# Buck_Converter.net
KiCad netlist of a schematic drawn in Altium Designer
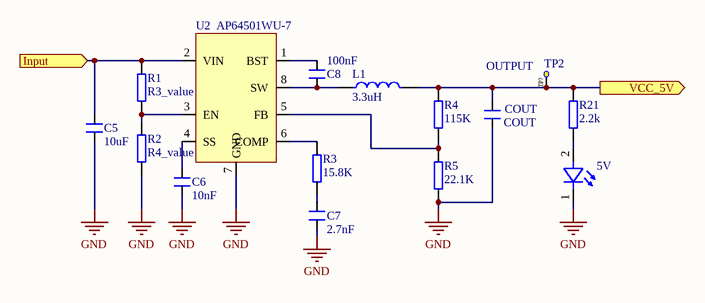
[diagram p0: Buck_Converter.SchDoc]

(export (version "E")
  (design (tool "Eeschema 10.0.6"))
  (components
    (comp (ref "5V") (value "led") (footprint "LED_fp") (libsource (lib "sch_comp") (part "led")))
    (comp (ref "C5") (value "10uF") (footprint "CAP_0805") (libsource (lib "sch_comp") (part "CAP_0805")))
    (comp (ref "C6") (value "10nF") (footprint "CAP_0805") (libsource (lib "sch_comp") (part "CAP_0805")))
    (comp (ref "C7") (value "2.7nF") (footprint "CAP_0805") (libsource (lib "sch_comp") (part "CAP_0805")))
    (comp (ref "C8") (value "100nF") (footprint "CAP_0805") (libsource (lib "sch_comp") (part "CAP_0805")))
    (comp (ref "COUT") (value "COUT") (footprint "CAP_0805") (libsource (lib "sch_comp") (part "CAP_0805")))
    (comp (ref "L1")
      (value "3.3uH")
      (footprint "SRN6045TA330M")
      (description "SRN6045TA-3R3Y")
      (libsource (lib "sch_comp") (part "Inductor"))
    )
    (comp (ref "R1") (value "R3_value") (footprint "RES0402") (libsource (lib "sch_comp") (part "RES 0402")))
    (comp (ref "R2") (value "R4_value") (footprint "RES0402") (libsource (lib "sch_comp") (part "RES 0402")))
    (comp (ref "R3") (value "15.8K") (footprint "RES0402") (libsource (lib "sch_comp") (part "RES 0402")))
    (comp (ref "R4") (value "115K") (footprint "RES0402") (libsource (lib "sch_comp") (part "RES 0402")))
    (comp (ref "R5") (value "22.1K") (footprint "RES0402") (libsource (lib "sch_comp") (part "RES 0402")))
    (comp (ref "R21") (value "2.2k") (footprint "RES0402") (libsource (lib "sch_comp") (part "RES 0402")))
    (comp (ref "TP2")
      (value "test_point")
      (footprint "Test_point")
      (libsource (lib "sch_comp") (part "test_point"))
    )
    (comp (ref "U2")
      (value "AP64501WU-7")
      (footprint "AP60501")
      (fields (field (name "MANUFACTURER") "Diodes") (field (name "MANUFACTURER PART NUMBER") "AP64060WU-7"))
      (libsource (lib "sch_comp") (part "AP64501WU-7"))
    )
  )
  (nets
    (net (code "1") (name "/Input") (class "Default")
      (node (ref "C5") (pin "2") (pintype "passive"))
      (node (ref "R1") (pin "2") (pintype "passive"))
      (node (ref "U2") (pin "2") (pinfunction "VIN_2") (pintype "passive"))
    )
    (net (code "2") (name "/VCC_5V") (class "Default")
      (node (ref "COUT") (pin "2") (pintype "passive"))
      (node (ref "L1") (pin "2") (pinfunction "2_2") (pintype "passive"))
      (node (ref "R21") (pin "2") (pintype "passive"))
      (node (ref "R4") (pin "2") (pintype "passive"))
      (node (ref "TP2") (pin "TP?") (pinfunction "Test_Point_TP?") (pintype "passive"))
    )
    (net (code "3") (name "GND") (class "Default")
      (node (ref "5V") (pin "1") (pinfunction "8_1") (pintype "passive"))
      (node (ref "C5") (pin "1") (pintype "passive"))
      (node (ref "C6") (pin "1") (pintype "passive"))
      (node (ref "C7") (pin "1") (pintype "passive"))
      (node (ref "COUT") (pin "1") (pintype "passive"))
      (node (ref "R2") (pin "1") (pintype "passive"))
      (node (ref "R5") (pin "1") (pintype "passive"))
      (node (ref "U2") (pin "7") (pinfunction "GND_7") (pintype "passive"))
    )
    (net (code "4") (name "Net-(5V-9)") (class "Default")
      (node (ref "5V") (pin "2") (pinfunction "9_2") (pintype "passive"))
      (node (ref "R21") (pin "1") (pintype "passive"))
    )
    (net (code "5") (name "Net-(C7-Pad2)") (class "Default")
      (node (ref "C7") (pin "2") (pintype "passive"))
      (node (ref "R3") (pin "1") (pintype "passive"))
    )
    (net (code "6") (name "Net-(U2-BST)") (class "Default")
      (node (ref "C8") (pin "2") (pintype "passive"))
      (node (ref "U2") (pin "1") (pinfunction "BST_1") (pintype "passive"))
    )
    (net (code "7") (name "Net-(U2-COMP)") (class "Default")
      (node (ref "R3") (pin "2") (pintype "passive"))
      (node (ref "U2") (pin "6") (pinfunction "COMP_6") (pintype "passive"))
    )
    (net (code "8") (name "Net-(U2-EN)") (class "Default")
      (node (ref "R1") (pin "1") (pintype "passive"))
      (node (ref "R2") (pin "2") (pintype "passive"))
      (node (ref "U2") (pin "3") (pinfunction "EN_3") (pintype "passive"))
    )
    (net (code "9") (name "Net-(U2-FB)") (class "Default")
      (node (ref "R4") (pin "1") (pintype "passive"))
      (node (ref "R5") (pin "2") (pintype "passive"))
      (node (ref "U2") (pin "5") (pinfunction "FB_5") (pintype "passive"))
    )
    (net (code "10") (name "Net-(U2-SS)") (class "Default")
      (node (ref "C6") (pin "2") (pintype "passive"))
      (node (ref "U2") (pin "4") (pinfunction "SS_4") (pintype "passive"))
    )
    (net (code "11") (name "Net-(U2-SW)") (class "Default")
      (node (ref "C8") (pin "1") (pintype "passive"))
      (node (ref "L1") (pin "1") (pinfunction "1_1") (pintype "passive"))
      (node (ref "U2") (pin "8") (pinfunction "SW_8") (pintype "passive"))
    )
  )
)
